# 5V-to-12V-Converter-alt.net
KiCad netlist of a schematic drawn in EAGLE
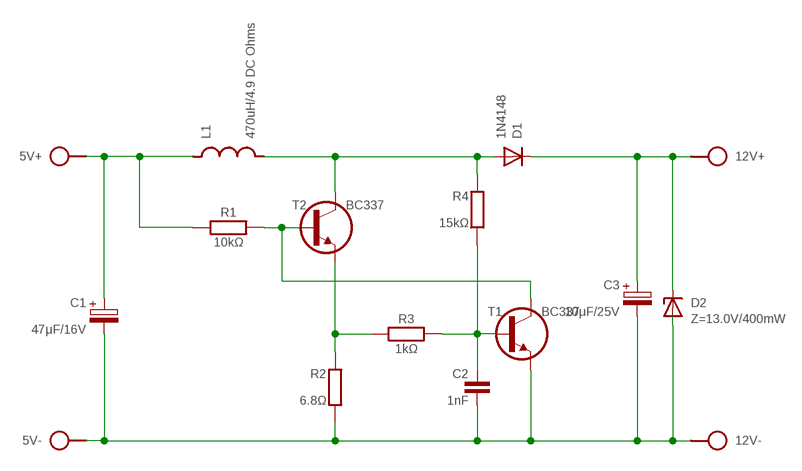
[diagram p0: schematic, sheet 1]

(export (version "E")
  (design (tool "Eeschema 10.0.6"))
  (components
    (comp (ref "5V")
      (value "SPAD+--+")
      (footprint "eagle-import:SPAD-+")
      (libsource (lib "eagle-import") (part "SPAD+--+"))
    )
    (comp (ref "12V")
      (value "SPAD+--+")
      (footprint "eagle-import:SPAD-+")
      (libsource (lib "eagle-import") (part "SPAD+--+"))
    )
    (comp (ref "C1")
      (value "47μF/16V")
      (footprint "eagle-import:E2.5-4_V")
      (libsource (lib "eagle-import") (part "CPOLE2,5-4/V"))
    )
    (comp (ref "C2")
      (value "1nF")
      (footprint "eagle-import:C050-020X036")
      (libsource (lib "eagle-import") (part "C050-020X036"))
    )
    (comp (ref "C3")
      (value "10μF/25V")
      (footprint "eagle-import:E2.5-4_V")
      (libsource (lib "eagle-import") (part "CPOLE2,5-4/V"))
    )
    (comp (ref "D1")
      (value "1N4148")
      (footprint "eagle-import:DO35-2_54A")
      (libsource (lib "eagle-import") (part "1N414835-2.54A"))
    )
    (comp (ref "D2")
      (value "Z=13.0V/400mW")
      (footprint "eagle-import:DO34Z12V")
      (libsource (lib "eagle-import") (part "Z-DIODE34Z12V"))
    )
    (comp (ref "L1")
      (value "470uH/4.9 DC Ohms")
      (footprint "eagle-import:ED16-X")
      (libsource (lib "eagle-import") (part "L-SHORTED16-X"))
    )
    (comp (ref "R1")
      (value "10kΩ")
      (footprint "eagle-import:0204_10")
      (libsource (lib "eagle-import") (part "R-H0204/10"))
    )
    (comp (ref "R2")
      (value "6.8Ω")
      (footprint "eagle-import:0204_10")
      (libsource (lib "eagle-import") (part "R0204/10"))
    )
    (comp (ref "R3")
      (value "1kΩ")
      (footprint "eagle-import:0204_10")
      (libsource (lib "eagle-import") (part "R-H0204/10"))
    )
    (comp (ref "R4")
      (value "15kΩ")
      (footprint "eagle-import:0204_10")
      (libsource (lib "eagle-import") (part "R0204/10"))
    )
    (comp (ref "T1")
      (value "BC337")
      (footprint "eagle-import:TO92-CBE")
      (libsource (lib "eagle-import") (part "BC337CBE"))
    )
    (comp (ref "T2")
      (value "BC337")
      (footprint "eagle-import:TO92-CBE")
      (libsource (lib "eagle-import") (part "BC337CBE"))
    )
  )
  (nets
    (net (code "1") (name "/N$18") (class "Default")
      (node (ref "5V") (pin "2") (pinfunction "P$1_2") (pintype "passive"))
      (node (ref "C1") (pin "+") (pinfunction "+_+") (pintype "passive"))
      (node (ref "D1") (pin "A") (pinfunction "A_A") (pintype "passive"))
      (node (ref "L1") (pin "1") (pinfunction "1_1") (pintype "passive"))
      (node (ref "L1") (pin "2") (pinfunction "2_2") (pintype "passive"))
      (node (ref "R1") (pin "1") (pinfunction "1_1") (pintype "passive"))
      (node (ref "R4") (pin "2") (pinfunction "1_2") (pintype "passive"))
      (node (ref "T2") (pin "C") (pinfunction "C_C") (pintype "passive"))
    )
    (net (code "2") (name "Net-(12VA-P$1)") (class "Default")
      (node (ref "12V") (pin "2") (pinfunction "P$1_2") (pintype "passive"))
      (node (ref "C3") (pin "+") (pinfunction "+_+") (pintype "passive"))
      (node (ref "D1") (pin "C") (pinfunction "C_C") (pintype "passive"))
      (node (ref "D2") (pin "C") (pinfunction "C_C") (pintype "passive"))
    )
    (net (code "3") (name "Net-(12VB-P$1)") (class "Default")
      (node (ref "12V") (pin "1") (pinfunction "P$1_1") (pintype "passive"))
      (node (ref "5V") (pin "1") (pinfunction "P$1_1") (pintype "passive"))
      (node (ref "C1") (pin "-") (pinfunction "-_-") (pintype "passive"))
      (node (ref "C2") (pin "2") (pinfunction "2_2") (pintype "passive"))
      (node (ref "C3") (pin "-") (pinfunction "-_-") (pintype "passive"))
      (node (ref "D2") (pin "A") (pinfunction "A_A") (pintype "passive"))
      (node (ref "R2") (pin "1") (pinfunction "2_1") (pintype "passive"))
      (node (ref "T1") (pin "E") (pinfunction "E_E") (pintype "passive"))
    )
    (net (code "4") (name "Net-(R1-Pad2)") (class "Default")
      (node (ref "R1") (pin "2") (pinfunction "2_2") (pintype "passive"))
      (node (ref "T1") (pin "C") (pinfunction "C_C") (pintype "passive"))
      (node (ref "T2") (pin "B") (pinfunction "B_B") (pintype "passive"))
    )
    (net (code "5") (name "Net-(R2-1)") (class "Default")
      (node (ref "R2") (pin "2") (pinfunction "1_2") (pintype "passive"))
      (node (ref "R3") (pin "1") (pinfunction "1_1") (pintype "passive"))
      (node (ref "T2") (pin "E") (pinfunction "E_E") (pintype "passive"))
    )
    (net (code "6") (name "Net-(R4-2)") (class "Default")
      (node (ref "C2") (pin "1") (pinfunction "1_1") (pintype "passive"))
      (node (ref "R3") (pin "2") (pinfunction "2_2") (pintype "passive"))
      (node (ref "R4") (pin "1") (pinfunction "2_1") (pintype "passive"))
      (node (ref "T1") (pin "B") (pinfunction "B_B") (pintype "passive"))
    )
  )
)
